# untitled.net
KiCad netlist of a schematic drawn in EAGLE
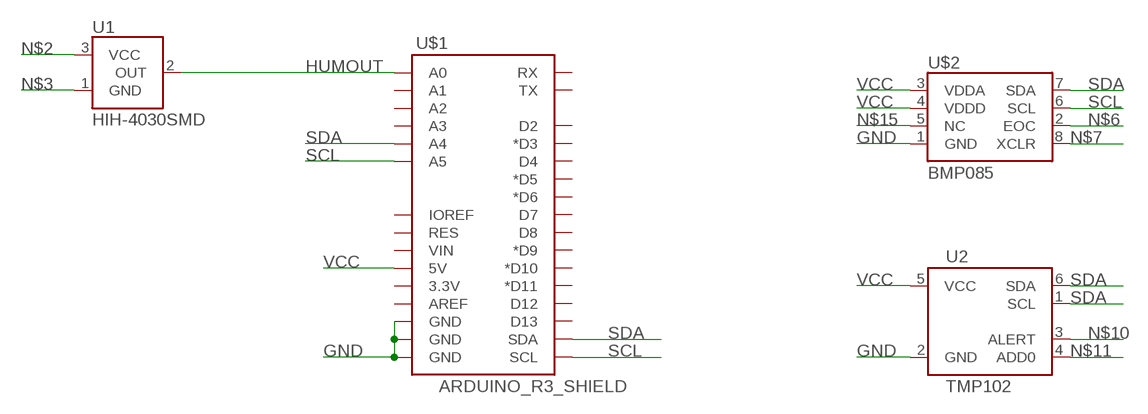
[diagram p0: schematic, sheet 1]

(export (version "E")
  (design (tool "Eeschema 10.0.6"))
  (components
    (comp (ref "U$1")
      (value "ARDUINO_R3_SHIELD")
      (footprint "eagle-import:UNO_R3_SHIELD")
      (libsource (lib "eagle-import") (part "ARDUINO_R3_SHIELD"))
    )
    (comp (ref "U$2")
      (value "BMP085")
      (footprint "eagle-import:BMP085")
      (libsource (lib "eagle-import") (part "BMP085"))
    )
    (comp (ref "U1")
      (value "HIH-4030SMD")
      (footprint "eagle-import:HIH-4030")
      (libsource (lib "eagle-import") (part "HIH-4030SMD"))
    )
    (comp (ref "U2")
      (value "TMP102")
      (footprint "eagle-import:SOT563")
      (libsource (lib "eagle-import") (part "TMP102"))
    )
  )
  (nets
    (net (code "1") (name "/GND") (class "Default")
      (node (ref "U$1") (pin "GND@0") (pinfunction "GND_GND@0") (pintype "bidirectional"))
      (node (ref "U$1") (pin "GND@1") (pinfunction "GND_GND@1") (pintype "bidirectional"))
      (node (ref "U$1") (pin "GND@2") (pinfunction "GND_GND@2") (pintype "bidirectional"))
      (node (ref "U$2") (pin "1") (pinfunction "GND_1") (pintype "power_in"))
      (node (ref "U2") (pin "2") (pinfunction "GND_2") (pintype "bidirectional"))
    )
    (net (code "2") (name "/HUMOUT") (class "Default")
      (node (ref "U$1") (pin "A0") (pinfunction "A0_A0") (pintype "bidirectional"))
      (node (ref "U1") (pin "2") (pinfunction "OUT_2") (pintype "bidirectional"))
    )
    (net (code "3") (name "/N$2") (class "Default")
      (node (ref "U1") (pin "3") (pinfunction "VCC_3") (pintype "bidirectional"))
    )
    (net (code "4") (name "/N$3") (class "Default")
      (node (ref "U1") (pin "1") (pinfunction "GND_1") (pintype "bidirectional"))
    )
    (net (code "5") (name "/N$6") (class "Default")
      (node (ref "U$2") (pin "2") (pinfunction "EOC_2") (pintype "output"))
    )
    (net (code "6") (name "/N$7") (class "Default")
      (node (ref "U$2") (pin "8") (pinfunction "XCLR_8") (pintype "input"))
    )
    (net (code "7") (name "/N$10") (class "Default")
      (node (ref "U2") (pin "3") (pinfunction "ALERT_3") (pintype "bidirectional"))
    )
    (net (code "8") (name "/N$11") (class "Default")
      (node (ref "U2") (pin "4") (pinfunction "ADD0_4") (pintype "bidirectional"))
    )
    (net (code "9") (name "/N$15") (class "Default")
      (node (ref "U$2") (pin "5") (pinfunction "NC_5") (pintype "bidirectional"))
    )
    (net (code "10") (name "/SCL") (class "Default")
      (node (ref "U$1") (pin "A5") (pinfunction "A5_A5") (pintype "bidirectional"))
      (node (ref "U$1") (pin "SCL") (pinfunction "SCL_SCL") (pintype "bidirectional"))
      (node (ref "U$2") (pin "6") (pinfunction "SCL_6") (pintype "input"))
    )
    (net (code "11") (name "/SDA") (class "Default")
      (node (ref "U$1") (pin "A4") (pinfunction "A4_A4") (pintype "bidirectional"))
      (node (ref "U$1") (pin "SDA") (pinfunction "SDA_SDA") (pintype "bidirectional"))
      (node (ref "U$2") (pin "7") (pinfunction "SDA_7") (pintype "bidirectional"))
      (node (ref "U2") (pin "1") (pinfunction "SCL_1") (pintype "bidirectional"))
      (node (ref "U2") (pin "6") (pinfunction "SDA_6") (pintype "bidirectional"))
    )
    (net (code "12") (name "/VCC") (class "Default")
      (node (ref "U$1") (pin "5V") (pinfunction "5V_5V") (pintype "bidirectional"))
      (node (ref "U$2") (pin "3") (pinfunction "VDDA_3") (pintype "power_in"))
      (node (ref "U$2") (pin "4") (pinfunction "VDDD_4") (pintype "power_in"))
      (node (ref "U2") (pin "5") (pinfunction "VCC_5") (pintype "bidirectional"))
    )
    (net (code "13") (name "unconnected-(U$1-*D3-PadD3)") (class "Default")
      (node (ref "U$1") (pin "D3") (pinfunction "*D3_D3") (pintype "bidirectional"))
    )
    (net (code "14") (name "unconnected-(U$1-*D5-PadD5)") (class "Default")
      (node (ref "U$1") (pin "D5") (pinfunction "*D5_D5") (pintype "bidirectional"))
    )
    (net (code "15") (name "unconnected-(U$1-*D6-PadD6)") (class "Default")
      (node (ref "U$1") (pin "D6") (pinfunction "*D6_D6") (pintype "bidirectional"))
    )
    (net (code "16") (name "unconnected-(U$1-*D9-PadD9)") (class "Default")
      (node (ref "U$1") (pin "D9") (pinfunction "*D9_D9") (pintype "bidirectional"))
    )
    (net (code "17") (name "unconnected-(U$1-*D10-PadD10)") (class "Default")
      (node (ref "U$1") (pin "D10") (pinfunction "*D10_D10") (pintype "bidirectional"))
    )
    (net (code "18") (name "unconnected-(U$1-*D11-PadD11)") (class "Default")
      (node (ref "U$1") (pin "D11") (pinfunction "*D11_D11") (pintype "bidirectional"))
    )
    (net (code "19") (name "unconnected-(U$1-Pad3.3V)") (class "Default")
      (node (ref "U$1") (pin "3.3V") (pinfunction "3.3V_3.3V") (pintype "bidirectional"))
    )
    (net (code "20") (name "unconnected-(U$1-PadA1)") (class "Default")
      (node (ref "U$1") (pin "A1") (pinfunction "A1_A1") (pintype "bidirectional"))
    )
    (net (code "21") (name "unconnected-(U$1-PadA2)") (class "Default")
      (node (ref "U$1") (pin "A2") (pinfunction "A2_A2") (pintype "bidirectional"))
    )
    (net (code "22") (name "unconnected-(U$1-PadA3)") (class "Default")
      (node (ref "U$1") (pin "A3") (pinfunction "A3_A3") (pintype "bidirectional"))
    )
    (net (code "23") (name "unconnected-(U$1-PadAREF)") (class "Default")
      (node (ref "U$1") (pin "AREF") (pinfunction "AREF_AREF") (pintype "bidirectional"))
    )
    (net (code "24") (name "unconnected-(U$1-PadD2)") (class "Default")
      (node (ref "U$1") (pin "D2") (pinfunction "D2_D2") (pintype "bidirectional"))
    )
    (net (code "25") (name "unconnected-(U$1-PadD4)") (class "Default")
      (node (ref "U$1") (pin "D4") (pinfunction "D4_D4") (pintype "bidirectional"))
    )
    (net (code "26") (name "unconnected-(U$1-PadD7)") (class "Default")
      (node (ref "U$1") (pin "D7") (pinfunction "D7_D7") (pintype "bidirectional"))
    )
    (net (code "27") (name "unconnected-(U$1-PadD8)") (class "Default")
      (node (ref "U$1") (pin "D8") (pinfunction "D8_D8") (pintype "bidirectional"))
    )
    (net (code "28") (name "unconnected-(U$1-PadD12)") (class "Default")
      (node (ref "U$1") (pin "D12") (pinfunction "D12_D12") (pintype "bidirectional"))
    )
    (net (code "29") (name "unconnected-(U$1-PadD13)") (class "Default")
      (node (ref "U$1") (pin "D13") (pinfunction "D13_D13") (pintype "bidirectional"))
    )
    (net (code "30") (name "unconnected-(U$1-PadIOREF)") (class "Default")
      (node (ref "U$1") (pin "IOREF") (pinfunction "IOREF_IOREF") (pintype "bidirectional"))
    )
    (net (code "31") (name "unconnected-(U$1-PadRES)") (class "Default")
      (node (ref "U$1") (pin "RES") (pinfunction "RES_RES") (pintype "bidirectional"))
    )
    (net (code "32") (name "unconnected-(U$1-PadRX)") (class "Default")
      (node (ref "U$1") (pin "RX") (pinfunction "RX_RX") (pintype "bidirectional"))
    )
    (net (code "33") (name "unconnected-(U$1-PadTX)") (class "Default")
      (node (ref "U$1") (pin "TX") (pinfunction "TX_TX") (pintype "bidirectional"))
    )
    (net (code "34") (name "unconnected-(U$1-PadVIN)") (class "Default")
      (node (ref "U$1") (pin "VIN") (pinfunction "VIN_VIN") (pintype "bidirectional"))
    )
  )
)
